# PCB_Telemetria_2020.net
KiCad netlist of a schematic drawn in EAGLE
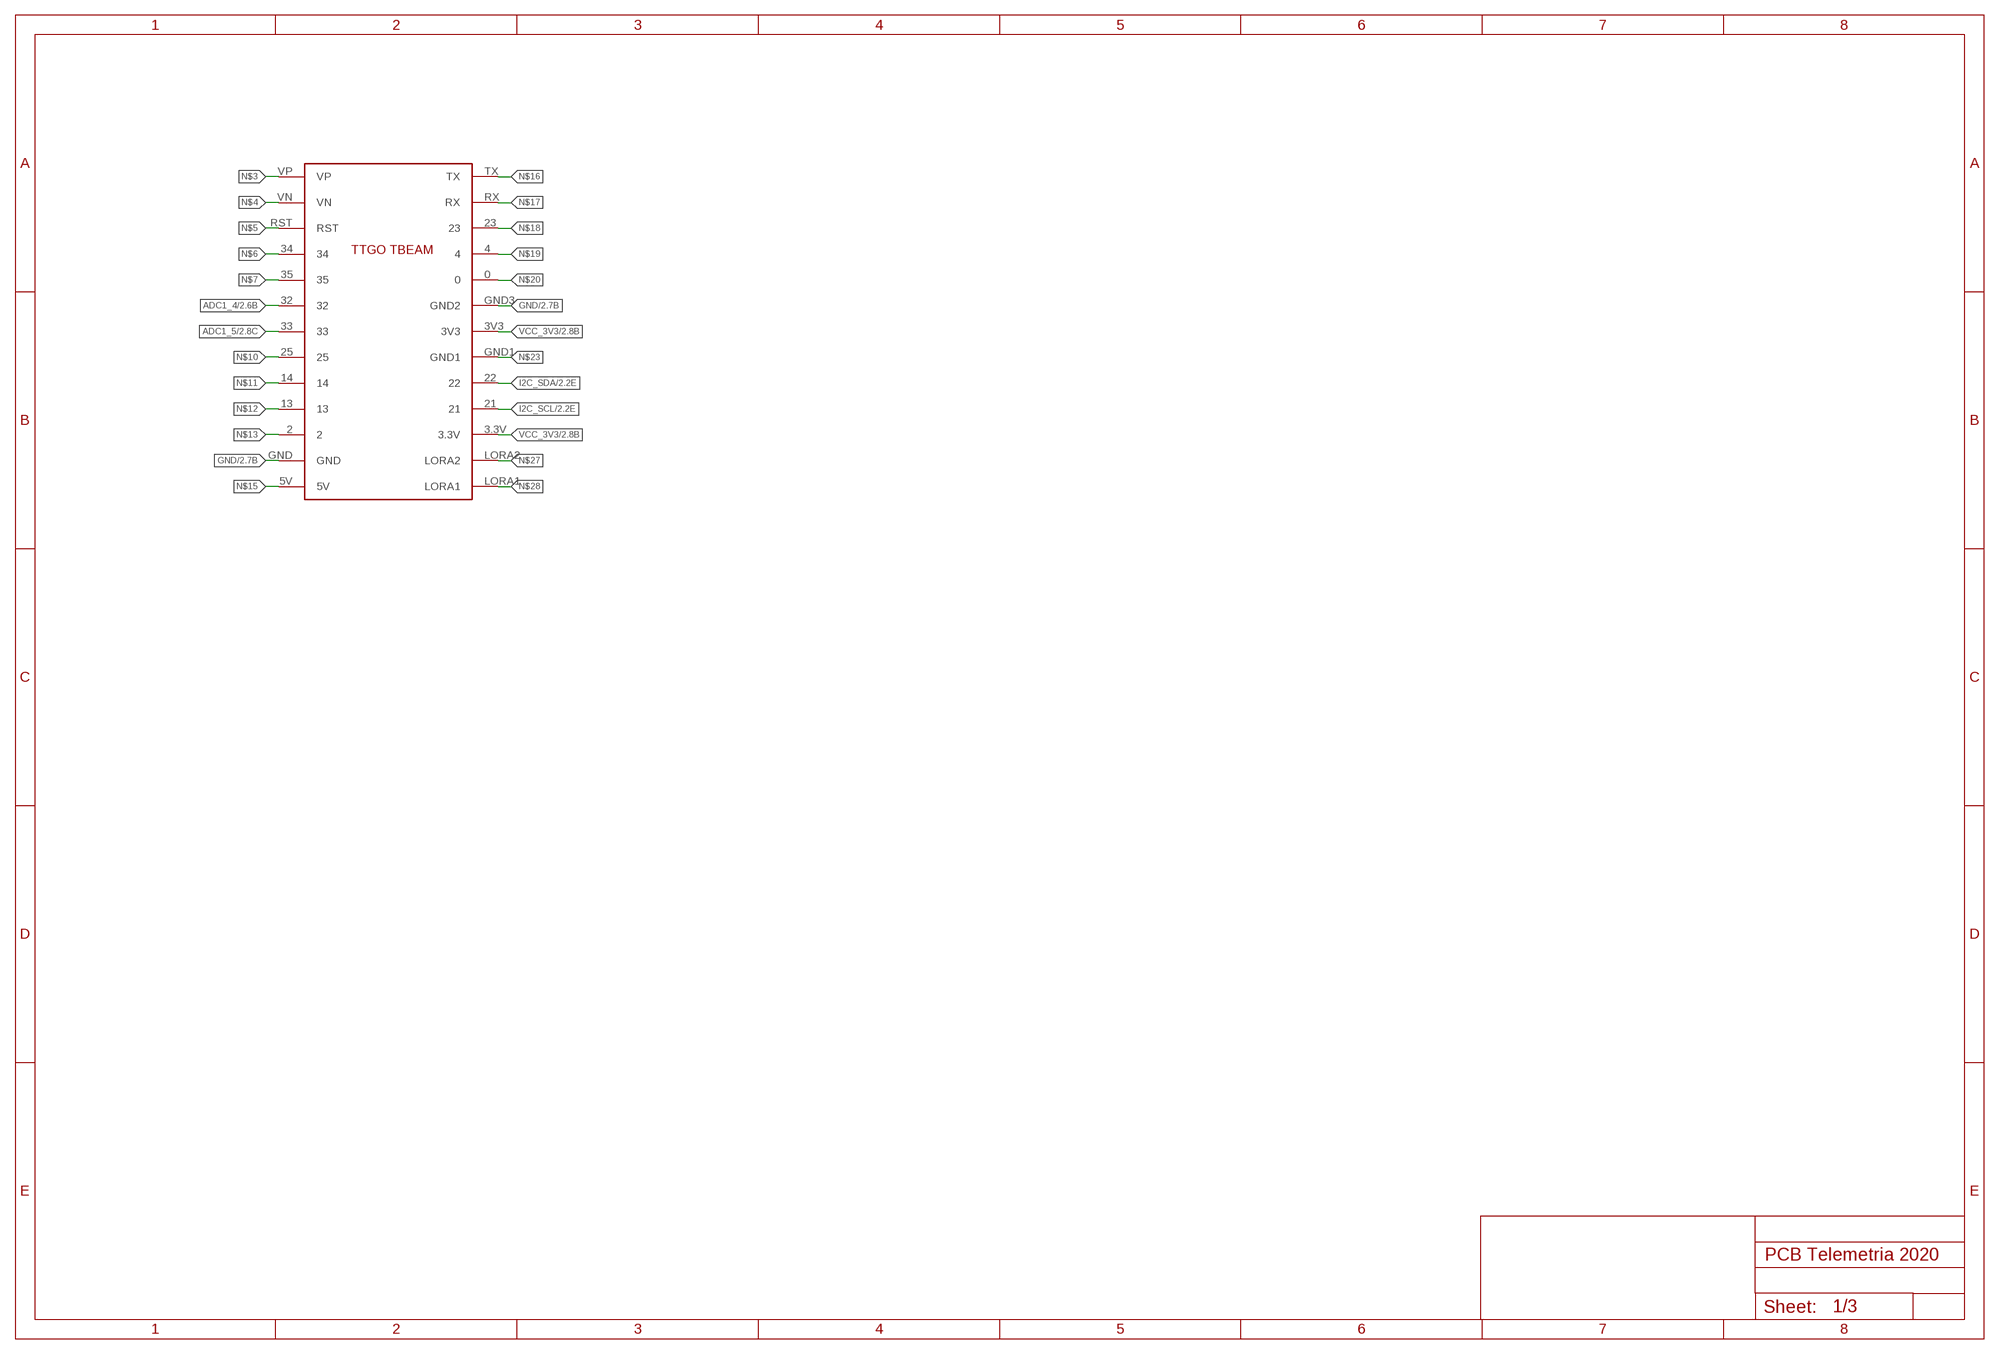
[diagram p0: schematic, sheet 1]
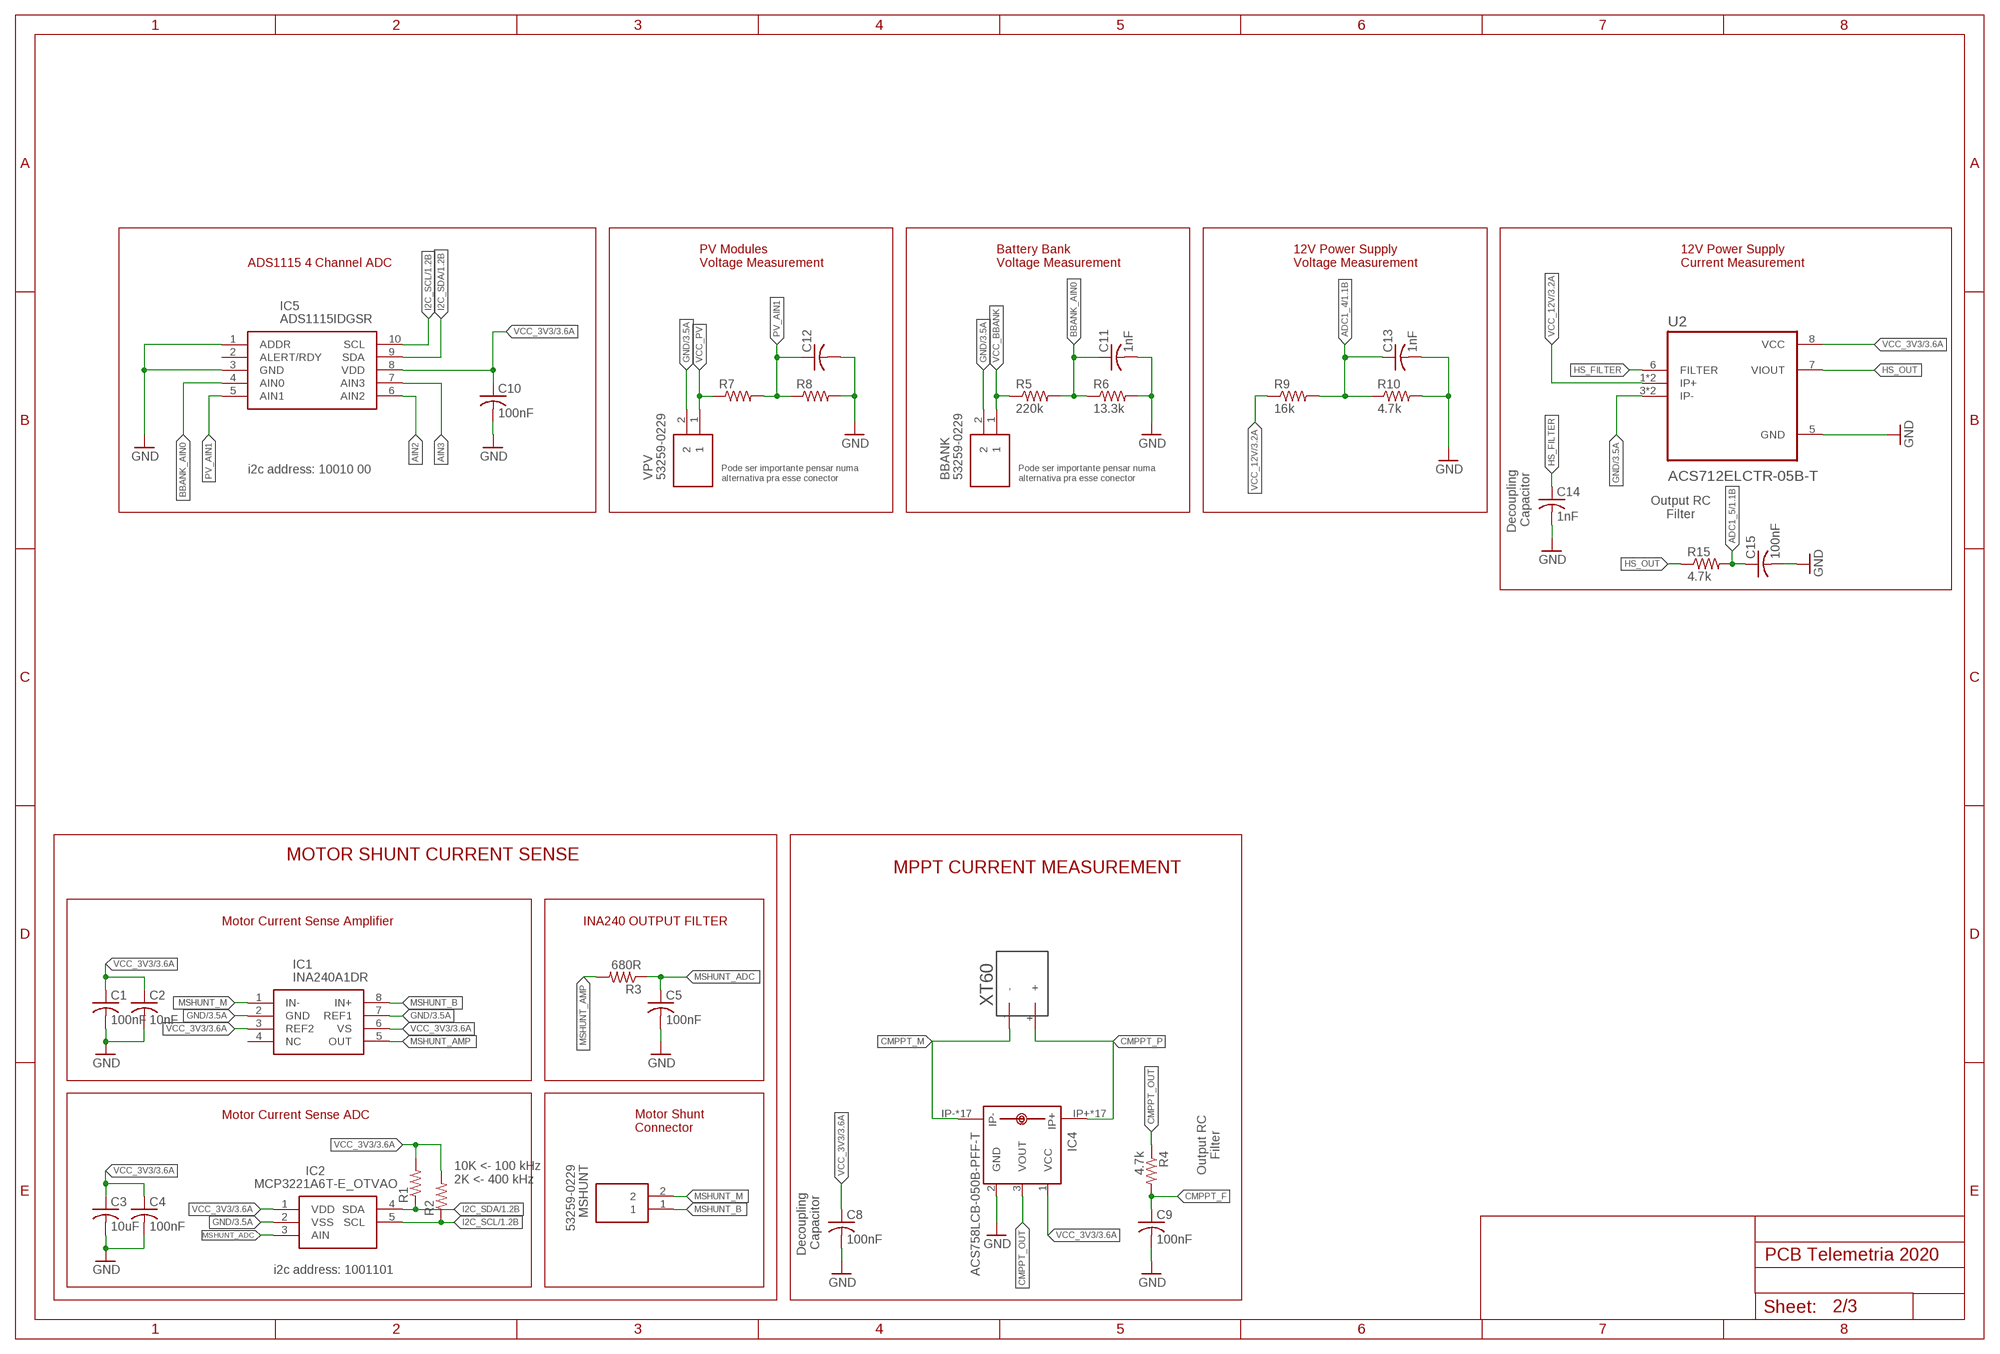
[diagram p1: schematic, sheet 2]
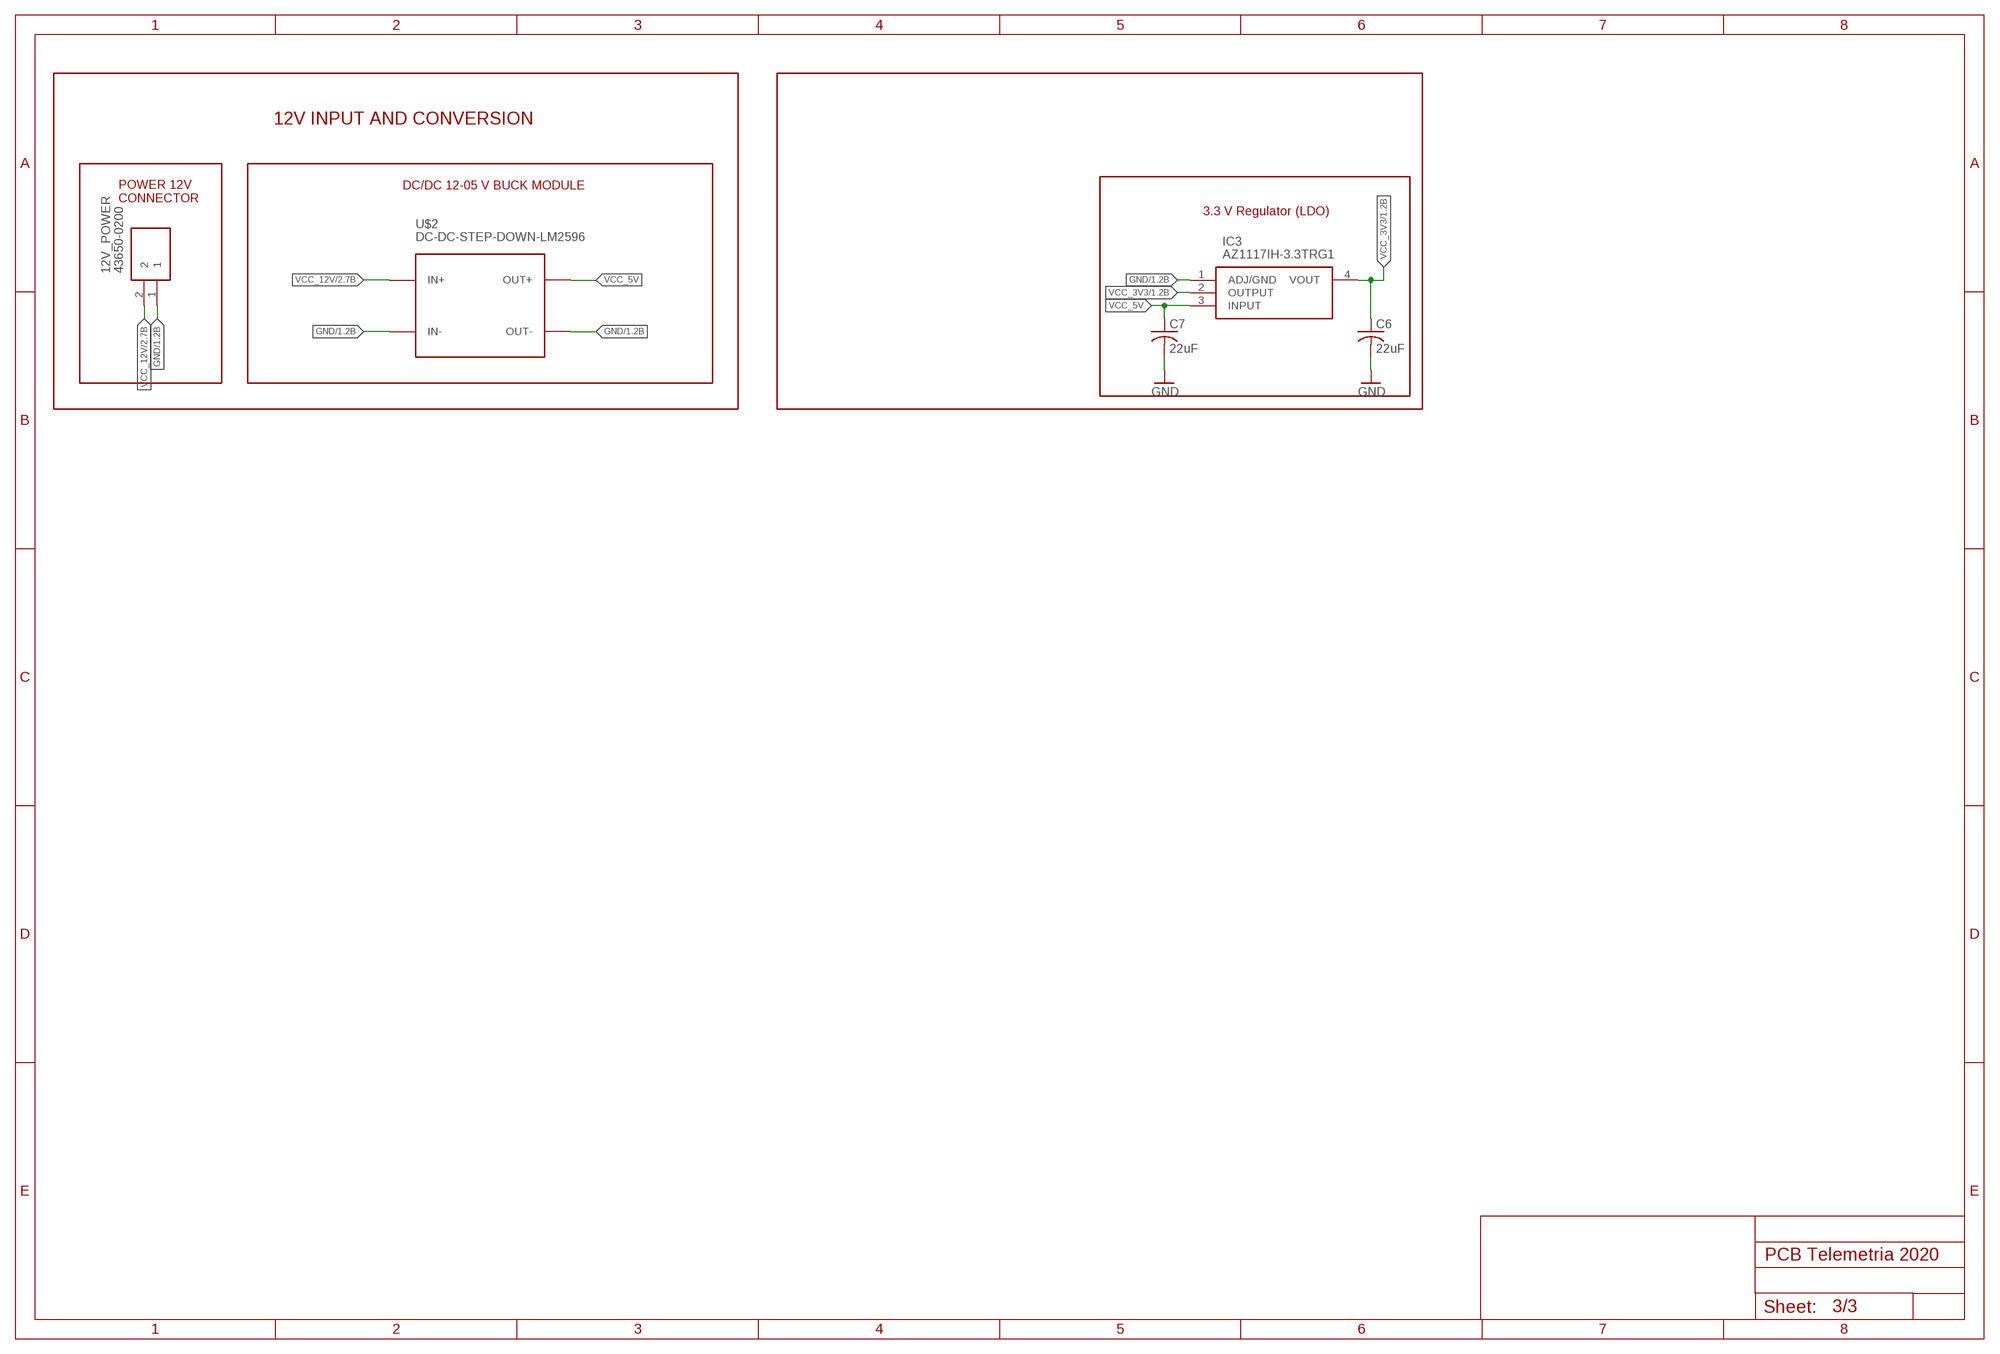
[diagram p2: schematic, sheet 3]

(export (version "E")
  (design (tool "Eeschema 10.0.6"))
  (components
    (comp (ref "BBANK")
      (value "53259-0229")
      (footprint "eagle-import:0532590229")
      (fields (field (name "MOUSER_PART_NUMBER") "538-53259-0229"))
      (libsource (lib "eagle-import") (part "53259-0229"))
    )
    (comp (ref "C1")
      (value "100nF")
      (footprint "eagle-import:C0805")
      (libsource (lib "eagle-import") (part "C-USC0805"))
    )
    (comp (ref "C2")
      (value "10nF")
      (footprint "eagle-import:C0805")
      (libsource (lib "eagle-import") (part "C-USC0805"))
    )
    (comp (ref "C3")
      (value "10uF")
      (footprint "eagle-import:C0805")
      (libsource (lib "eagle-import") (part "C-USC0805"))
    )
    (comp (ref "C4")
      (value "100nF")
      (footprint "eagle-import:C0805")
      (libsource (lib "eagle-import") (part "C-USC0805"))
    )
    (comp (ref "C5")
      (value "100nF")
      (footprint "eagle-import:C0805")
      (libsource (lib "eagle-import") (part "C-USC0805"))
    )
    (comp (ref "C8")
      (value "100nF")
      (footprint "eagle-import:C0805")
      (libsource (lib "eagle-import") (part "C-USC0805"))
    )
    (comp (ref "C9")
      (value "100nF")
      (footprint "eagle-import:C0805")
      (libsource (lib "eagle-import") (part "C-USC0805"))
    )
    (comp (ref "C10")
      (value "100nF")
      (footprint "eagle-import:C0805")
      (libsource (lib "eagle-import") (part "C-USC0805"))
    )
    (comp (ref "C11")
      (value "1nF")
      (footprint "eagle-import:C0805")
      (libsource (lib "eagle-import") (part "C-USC0805"))
    )
    (comp (ref "C12")
      (value "C-USC0805")
      (footprint "eagle-import:C0805")
      (libsource (lib "eagle-import") (part "C-USC0805"))
    )
    (comp (ref "C13")
      (value "1nF")
      (footprint "eagle-import:C0805")
      (libsource (lib "eagle-import") (part "C-USC0805"))
    )
    (comp (ref "C14")
      (value "1nF")
      (footprint "eagle-import:C0805")
      (libsource (lib "eagle-import") (part "C-USC0805"))
    )
    (comp (ref "C15")
      (value "100nF")
      (footprint "eagle-import:C0805")
      (libsource (lib "eagle-import") (part "C-USC0805"))
    )
    (comp (ref "IC1")
      (value "INA240A1DR")
      (footprint "eagle-import:SOIC127P600X175-8N")
      (fields (field (name "MOUSER_PART_NUMBER") "595-INA240A1DR"))
      (libsource (lib "eagle-import") (part "INA240A1DR"))
    )
    (comp (ref "IC2")
      (value "MCP3221A6T-E_OTVAO")
      (footprint "eagle-import:SOT95P280X145-5N")
      (fields
        (field (name "MANUFACTURER_PART_NUMBER") "MCP3221A6T-E/OTVAO")
        (field (name "MOUSER_PART_NUMBER") "579-MCP3221A6TEOTVAO")
      )
      (libsource (lib "eagle-import") (part "MCP3221A6T-E_OTVAO"))
    )
    (comp (ref "IC4")
      (value "ACS758LCB-050B-PFF-T")
      (footprint "eagle-import:CB-PFF")
      (libsource (lib "eagle-import") (part "ACS758LCB-050B-PFF-T"))
    )
    (comp (ref "IC5")
      (value "ADS1115IDGSR")
      (footprint "eagle-import:SOP50P490X110-10N")
      (fields (field (name "MOUSER_PART_NUMBER") "595-ADS1115IDGSR"))
      (libsource (lib "eagle-import") (part "ADS1115IDGSR"))
    )
    (comp (ref "MSHUNT")
      (value "53259-0229")
      (footprint "eagle-import:0532590229")
      (fields (field (name "MOUSER_PART_NUMBER") "538-53259-0229"))
      (libsource (lib "eagle-import") (part "53259-0229"))
    )
    (comp (ref "R1")
      (value "R-US_R0805")
      (footprint "eagle-import:R0805")
      (libsource (lib "eagle-import") (part "R-US_R0805"))
    )
    (comp (ref "R2")
      (value "R-US_R0805")
      (footprint "eagle-import:R0805")
      (libsource (lib "eagle-import") (part "R-US_R0805"))
    )
    (comp (ref "R3")
      (value "680R")
      (footprint "eagle-import:R0805")
      (libsource (lib "eagle-import") (part "R-US_R0805"))
    )
    (comp (ref "R4")
      (value "4.7k")
      (footprint "eagle-import:R0805")
      (libsource (lib "eagle-import") (part "R-US_R0805"))
    )
    (comp (ref "R5")
      (value "220k")
      (footprint "eagle-import:R0805")
      (libsource (lib "eagle-import") (part "R-US_R0805"))
    )
    (comp (ref "R6")
      (value "13.3k")
      (footprint "eagle-import:R0805")
      (libsource (lib "eagle-import") (part "R-US_R0805"))
    )
    (comp (ref "R7")
      (value "R-US_R0805")
      (footprint "eagle-import:R0805")
      (libsource (lib "eagle-import") (part "R-US_R0805"))
    )
    (comp (ref "R8")
      (value "R-US_R0805")
      (footprint "eagle-import:R0805")
      (libsource (lib "eagle-import") (part "R-US_R0805"))
    )
    (comp (ref "R9")
      (value "16k")
      (footprint "eagle-import:R0805")
      (libsource (lib "eagle-import") (part "R-US_R0805"))
    )
    (comp (ref "R10")
      (value "4.7k")
      (footprint "eagle-import:R0805")
      (libsource (lib "eagle-import") (part "R-US_R0805"))
    )
    (comp (ref "R15")
      (value "4.7k")
      (footprint "eagle-import:R0805")
      (libsource (lib "eagle-import") (part "R-US_R0805"))
    )
    (comp (ref "U$3")
      (value "XT60")
      (footprint "eagle-import:XT60")
      (libsource (lib "eagle-import") (part "XT60"))
    )
    (comp (ref "U2")
      (value "ACS712ELCTR-05B-T")
      (footprint "eagle-import:SOIC127P600X175-8N")
      (fields (field (name "MF") "Allegro MicroSystems LLC"))
      (libsource (lib "eagle-import") (part "ACS712ELCTR-05B-T"))
    )
    (comp (ref "VPV")
      (value "53259-0229")
      (footprint "eagle-import:0532590229")
      (fields (field (name "MOUSER_PART_NUMBER") "538-53259-0229"))
      (libsource (lib "eagle-import") (part "53259-0229"))
    )
    (comp (ref "U$1")
      (value "TTGOBEAM")
      (footprint "eagle-import:TTGOBEAM")
      (libsource (lib "eagle-import") (part "TTGOBEAM"))
    )
    (comp (ref "12V_POWER")
      (value "43650-0200")
      (footprint "eagle-import:43650-0200")
      (fields (field (name "MOUSER_PART_NUMBER") "538-43650-0200"))
      (libsource (lib "eagle-import") (part "43650-0200"))
    )
    (comp (ref "C6")
      (value "22uF")
      (footprint "eagle-import:C0805")
      (libsource (lib "eagle-import") (part "C-USC0805"))
    )
    (comp (ref "C7")
      (value "22uF")
      (footprint "eagle-import:C0805")
      (libsource (lib "eagle-import") (part "C-USC0805"))
    )
    (comp (ref "IC3")
      (value "AZ1117IH-3.3TRG1")
      (footprint "eagle-import:SOT230P700X170-4N")
      (fields (field (name "MOUSER_PART_NUMBER") "621-AZ1117IH-3.3TRG1"))
      (libsource (lib "eagle-import") (part "AZ1117IH-3.3TRG1"))
    )
    (comp (ref "U$2")
      (value "DC-DC-STEP-DOWN-LM2596")
      (footprint "eagle-import:DC-DC-STEP-DOWN-LM2596")
      (libsource (lib "eagle-import") (part "DC-DC-STEP-DOWN-LM2596"))
    )
  )
  (nets
    (net (code "1") (name "ADC1_4") (class "Default")
      (node (ref "C13") (pin "1") (pinfunction "1_1") (pintype "passive"))
      (node (ref "R10") (pin "1") (pinfunction "1_1") (pintype "passive"))
      (node (ref "R9") (pin "2") (pinfunction "2_2") (pintype "passive"))
      (node (ref "U$1") (pin "32") (pinfunction "32_32") (pintype "bidirectional"))
    )
    (net (code "2") (name "ADC1_5") (class "Default")
      (node (ref "C15") (pin "1") (pinfunction "1_1") (pintype "passive"))
      (node (ref "R15") (pin "2") (pinfunction "2_2") (pintype "passive"))
      (node (ref "U$1") (pin "33") (pinfunction "33_33") (pintype "bidirectional"))
    )
    (net (code "3") (name "AIN2") (class "Default")
      (node (ref "IC5") (pin "6") (pinfunction "AIN2_6") (pintype "bidirectional"))
    )
    (net (code "4") (name "AIN3") (class "Default")
      (node (ref "IC5") (pin "7") (pinfunction "AIN3_7") (pintype "bidirectional"))
    )
    (net (code "5") (name "BBANK_AIN0") (class "Default")
      (node (ref "C11") (pin "1") (pinfunction "1_1") (pintype "passive"))
      (node (ref "IC5") (pin "4") (pinfunction "AIN0_4") (pintype "bidirectional"))
      (node (ref "R5") (pin "2") (pinfunction "2_2") (pintype "passive"))
      (node (ref "R6") (pin "1") (pinfunction "1_1") (pintype "passive"))
    )
    (net (code "6") (name "CMPPT_F") (class "Default")
      (node (ref "C9") (pin "1") (pinfunction "1_1") (pintype "passive"))
      (node (ref "R4") (pin "2") (pinfunction "2_2") (pintype "passive"))
    )
    (net (code "7") (name "CMPPT_M") (class "Default")
      (node (ref "IC4") (pin "IP-") (pinfunction "IP-_IP-") (pintype "passive"))
      (node (ref "IC4") (pin "IP-@10") (pinfunction "IP-_IP-@10") (pintype "passive"))
      (node (ref "IC4") (pin "IP-@11") (pinfunction "IP-_IP-@11") (pintype "passive"))
      (node (ref "IC4") (pin "IP-@12") (pinfunction "IP-_IP-@12") (pintype "passive"))
      (node (ref "IC4") (pin "IP-@13") (pinfunction "IP-_IP-@13") (pintype "passive"))
      (node (ref "IC4") (pin "IP-@14") (pinfunction "IP-_IP-@14") (pintype "passive"))
      (node (ref "IC4") (pin "IP-@15") (pinfunction "IP-_IP-@15") (pintype "passive"))
      (node (ref "IC4") (pin "IP-@16") (pinfunction "IP-_IP-@16") (pintype "passive"))
      (node (ref "IC4") (pin "IP-@17") (pinfunction "IP-_IP-@17") (pintype "passive"))
      (node (ref "IC4") (pin "IP-@2") (pinfunction "IP-_IP-@2") (pintype "passive"))
      (node (ref "IC4") (pin "IP-@3") (pinfunction "IP-_IP-@3") (pintype "passive"))
      (node (ref "IC4") (pin "IP-@4") (pinfunction "IP-_IP-@4") (pintype "passive"))
      (node (ref "IC4") (pin "IP-@5") (pinfunction "IP-_IP-@5") (pintype "passive"))
      (node (ref "IC4") (pin "IP-@6") (pinfunction "IP-_IP-@6") (pintype "passive"))
      (node (ref "IC4") (pin "IP-@7") (pinfunction "IP-_IP-@7") (pintype "passive"))
      (node (ref "IC4") (pin "IP-@8") (pinfunction "IP-_IP-@8") (pintype "passive"))
      (node (ref "IC4") (pin "IP-@9") (pinfunction "IP-_IP-@9") (pintype "passive"))
      (node (ref "U$3") (pin "-") (pinfunction "-_-") (pintype "bidirectional"))
    )
    (net (code "8") (name "CMPPT_OUT") (class "Default")
      (node (ref "IC4") (pin "3") (pinfunction "VOUT_3") (pintype "output"))
      (node (ref "R4") (pin "1") (pinfunction "1_1") (pintype "passive"))
    )
    (net (code "9") (name "CMPPT_P") (class "Default")
      (node (ref "IC4") (pin "IP+") (pinfunction "IP+_IP+") (pintype "passive"))
      (node (ref "IC4") (pin "IP+@10") (pinfunction "IP+_IP+@10") (pintype "passive"))
      (node (ref "IC4") (pin "IP+@11") (pinfunction "IP+_IP+@11") (pintype "passive"))
      (node (ref "IC4") (pin "IP+@12") (pinfunction "IP+_IP+@12") (pintype "passive"))
      (node (ref "IC4") (pin "IP+@13") (pinfunction "IP+_IP+@13") (pintype "passive"))
      (node (ref "IC4") (pin "IP+@14") (pinfunction "IP+_IP+@14") (pintype "passive"))
      (node (ref "IC4") (pin "IP+@15") (pinfunction "IP+_IP+@15") (pintype "passive"))
      (node (ref "IC4") (pin "IP+@16") (pinfunction "IP+_IP+@16") (pintype "passive"))
      (node (ref "IC4") (pin "IP+@17") (pinfunction "IP+_IP+@17") (pintype "passive"))
      (node (ref "IC4") (pin "IP+@2") (pinfunction "IP+_IP+@2") (pintype "passive"))
      (node (ref "IC4") (pin "IP+@3") (pinfunction "IP+_IP+@3") (pintype "passive"))
      (node (ref "IC4") (pin "IP+@4") (pinfunction "IP+_IP+@4") (pintype "passive"))
      (node (ref "IC4") (pin "IP+@5") (pinfunction "IP+_IP+@5") (pintype "passive"))
      (node (ref "IC4") (pin "IP+@6") (pinfunction "IP+_IP+@6") (pintype "passive"))
      (node (ref "IC4") (pin "IP+@7") (pinfunction "IP+_IP+@7") (pintype "passive"))
      (node (ref "IC4") (pin "IP+@8") (pinfunction "IP+_IP+@8") (pintype "passive"))
      (node (ref "IC4") (pin "IP+@9") (pinfunction "IP+_IP+@9") (pintype "passive"))
      (node (ref "U$3") (pin "+") (pinfunction "+_+") (pintype "bidirectional"))
    )
    (net (code "10") (name "GND") (class "Default")
      (node (ref "12V_POWER") (pin "1") (pinfunction "1_1") (pintype "bidirectional"))
      (node (ref "BBANK") (pin "2") (pinfunction "2_2") (pintype "bidirectional"))
      (node (ref "C1") (pin "2") (pinfunction "2_2") (pintype "passive"))
      (node (ref "C10") (pin "2") (pinfunction "2_2") (pintype "passive"))
      (node (ref "C11") (pin "2") (pinfunction "2_2") (pintype "passive"))
      (node (ref "C12") (pin "2") (pinfunction "2_2") (pintype "passive"))
      (node (ref "C13") (pin "2") (pinfunction "2_2") (pintype "passive"))
      (node (ref "C14") (pin "2") (pinfunction "2_2") (pintype "passive"))
      (node (ref "C15") (pin "2") (pinfunction "2_2") (pintype "passive"))
      (node (ref "C2") (pin "2") (pinfunction "2_2") (pintype "passive"))
      (node (ref "C3") (pin "2") (pinfunction "2_2") (pintype "passive"))
      (node (ref "C4") (pin "2") (pinfunction "2_2") (pintype "passive"))
      (node (ref "C5") (pin "2") (pinfunction "2_2") (pintype "passive"))
      (node (ref "C6") (pin "2") (pinfunction "2_2") (pintype "passive"))
      (node (ref "C7") (pin "2") (pinfunction "2_2") (pintype "passive"))
      (node (ref "C8") (pin "2") (pinfunction "2_2") (pintype "passive"))
      (node (ref "C9") (pin "2") (pinfunction "2_2") (pintype "passive"))
      (node (ref "IC1") (pin "2") (pinfunction "GND_2") (pintype "bidirectional"))
      (node (ref "IC1") (pin "7") (pinfunction "REF1_7") (pintype "bidirectional"))
      (node (ref "IC2") (pin "2") (pinfunction "VSS_2") (pintype "bidirectional"))
      (node (ref "IC3") (pin "1") (pinfunction "ADJ/GND_1") (pintype "bidirectional"))
      (node (ref "IC4") (pin "2") (pinfunction "GND_2") (pintype "power_in"))
      (node (ref "IC5") (pin "1") (pinfunction "ADDR_1") (pintype "bidirectional"))
      (node (ref "IC5") (pin "3") (pinfunction "GND_3") (pintype "bidirectional"))
      (node (ref "R10") (pin "2") (pinfunction "2_2") (pintype "passive"))
      (node (ref "R6") (pin "2") (pinfunction "2_2") (pintype "passive"))
      (node (ref "R8") (pin "2") (pinfunction "2_2") (pintype "passive"))
      (node (ref "U$1") (pin "GND") (pinfunction "GND_GND") (pintype "bidirectional"))
      (node (ref "U$1") (pin "GND3") (pinfunction "GND2_GND3") (pintype "bidirectional"))
      (node (ref "U$2") (pin "IN-") (pinfunction "IN-_IN-") (pintype "bidirectional"))
      (node (ref "U$2") (pin "OUT-") (pinfunction "OUT-_OUT-") (pintype "bidirectional"))
      (node (ref "U2") (pin "3") (pinfunction "IP-_3") (pintype "input"))
      (node (ref "U2") (pin "4") (pinfunction "IP-_4") (pintype "input"))
      (node (ref "U2") (pin "5") (pinfunction "GND_5") (pintype "power_in"))
      (node (ref "VPV") (pin "2") (pinfunction "2_2") (pintype "bidirectional"))
    )
    (net (code "11") (name "HS_FILTER") (class "Default")
      (node (ref "C14") (pin "1") (pinfunction "1_1") (pintype "passive"))
      (node (ref "U2") (pin "6") (pinfunction "FILTER_6") (pintype "input"))
    )
    (net (code "12") (name "HS_OUT") (class "Default")
      (node (ref "R15") (pin "1") (pinfunction "1_1") (pintype "passive"))
      (node (ref "U2") (pin "7") (pinfunction "VIOUT_7") (pintype "output"))
    )
    (net (code "13") (name "I2C_SCL") (class "Default")
      (node (ref "IC2") (pin "5") (pinfunction "SCL_5") (pintype "bidirectional"))
      (node (ref "IC5") (pin "10") (pinfunction "SCL_10") (pintype "bidirectional"))
      (node (ref "R2") (pin "1") (pinfunction "1_1") (pintype "passive"))
      (node (ref "U$1") (pin "21") (pinfunction "21_21") (pintype "bidirectional"))
    )
    (net (code "14") (name "I2C_SDA") (class "Default")
      (node (ref "IC2") (pin "4") (pinfunction "SDA_4") (pintype "bidirectional"))
      (node (ref "IC5") (pin "9") (pinfunction "SDA_9") (pintype "bidirectional"))
      (node (ref "R1") (pin "1") (pinfunction "1_1") (pintype "passive"))
      (node (ref "U$1") (pin "22") (pinfunction "22_22") (pintype "bidirectional"))
    )
    (net (code "15") (name "MSHUNT_ADC") (class "Default")
      (node (ref "C5") (pin "1") (pinfunction "1_1") (pintype "passive"))
      (node (ref "IC2") (pin "3") (pinfunction "AIN_3") (pintype "bidirectional"))
      (node (ref "R3") (pin "1") (pinfunction "1_1") (pintype "passive"))
    )
    (net (code "16") (name "MSHUNT_AMP") (class "Default")
      (node (ref "IC1") (pin "5") (pinfunction "OUT_5") (pintype "bidirectional"))
      (node (ref "R3") (pin "2") (pinfunction "2_2") (pintype "passive"))
    )
    (net (code "17") (name "MSHUNT_B") (class "Default")
      (node (ref "IC1") (pin "8") (pinfunction "IN+_8") (pintype "bidirectional"))
      (node (ref "MSHUNT") (pin "1") (pinfunction "1_1") (pintype "bidirectional"))
    )
    (net (code "18") (name "MSHUNT_M") (class "Default")
      (node (ref "IC1") (pin "1") (pinfunction "IN-_1") (pintype "bidirectional"))
      (node (ref "MSHUNT") (pin "2") (pinfunction "2_2") (pintype "bidirectional"))
    )
    (net (code "19") (name "N$3") (class "Default")
      (node (ref "U$1") (pin "VP") (pinfunction "VP_VP") (pintype "bidirectional"))
    )
    (net (code "20") (name "N$4") (class "Default")
      (node (ref "U$1") (pin "VN") (pinfunction "VN_VN") (pintype "bidirectional"))
    )
    (net (code "21") (name "N$5") (class "Default")
      (node (ref "U$1") (pin "RST") (pinfunction "RST_RST") (pintype "bidirectional"))
    )
    (net (code "22") (name "N$6") (class "Default")
      (node (ref "U$1") (pin "34") (pinfunction "34_34") (pintype "bidirectional"))
    )
    (net (code "23") (name "N$7") (class "Default")
      (node (ref "U$1") (pin "35") (pinfunction "35_35") (pintype "bidirectional"))
    )
    (net (code "24") (name "N$10") (class "Default")
      (node (ref "U$1") (pin "25") (pinfunction "25_25") (pintype "bidirectional"))
    )
    (net (code "25") (name "N$11") (class "Default")
      (node (ref "U$1") (pin "14") (pinfunction "14_14") (pintype "bidirectional"))
    )
    (net (code "26") (name "N$12") (class "Default")
      (node (ref "U$1") (pin "13") (pinfunction "13_13") (pintype "bidirectional"))
    )
    (net (code "27") (name "N$13") (class "Default")
      (node (ref "U$1") (pin "2") (pinfunction "2_2") (pintype "bidirectional"))
    )
    (net (code "28") (name "N$15") (class "Default")
      (node (ref "U$1") (pin "5V") (pinfunction "5V_5V") (pintype "bidirectional"))
    )
    (net (code "29") (name "N$16") (class "Default")
      (node (ref "U$1") (pin "TX") (pinfunction "TX_TX") (pintype "bidirectional"))
    )
    (net (code "30") (name "N$17") (class "Default")
      (node (ref "U$1") (pin "RX") (pinfunction "RX_RX") (pintype "bidirectional"))
    )
    (net (code "31") (name "N$18") (class "Default")
      (node (ref "U$1") (pin "23") (pinfunction "23_23") (pintype "bidirectional"))
    )
    (net (code "32") (name "N$19") (class "Default")
      (node (ref "U$1") (pin "4") (pinfunction "4_4") (pintype "bidirectional"))
    )
    (net (code "33") (name "N$20") (class "Default")
      (node (ref "U$1") (pin "0") (pinfunction "0_0") (pintype "bidirectional"))
    )
    (net (code "34") (name "N$23") (class "Default")
      (node (ref "U$1") (pin "GND1") (pinfunction "GND1_GND1") (pintype "bidirectional"))
    )
    (net (code "35") (name "N$27") (class "Default")
      (node (ref "U$1") (pin "LORA2") (pinfunction "LORA2_LORA2") (pintype "bidirectional"))
    )
    (net (code "36") (name "N$28") (class "Default")
      (node (ref "U$1") (pin "LORA1") (pinfunction "LORA1_LORA1") (pintype "bidirectional"))
    )
    (net (code "37") (name "PV_AIN1") (class "Default")
      (node (ref "C12") (pin "1") (pinfunction "1_1") (pintype "passive"))
      (node (ref "IC5") (pin "5") (pinfunction "AIN1_5") (pintype "bidirectional"))
      (node (ref "R7") (pin "2") (pinfunction "2_2") (pintype "passive"))
      (node (ref "R8") (pin "1") (pinfunction "1_1") (pintype "passive"))
    )
    (net (code "38") (name "VCC_3V3") (class "Default")
      (node (ref "C1") (pin "1") (pinfunction "1_1") (pintype "passive"))
      (node (ref "C10") (pin "1") (pinfunction "1_1") (pintype "passive"))
      (node (ref "C2") (pin "1") (pinfunction "1_1") (pintype "passive"))
      (node (ref "C3") (pin "1") (pinfunction "1_1") (pintype "passive"))
      (node (ref "C4") (pin "1") (pinfunction "1_1") (pintype "passive"))
      (node (ref "C6") (pin "1") (pinfunction "1_1") (pintype "passive"))
      (node (ref "C8") (pin "1") (pinfunction "1_1") (pintype "passive"))
      (node (ref "IC1") (pin "3") (pinfunction "REF2_3") (pintype "bidirectional"))
      (node (ref "IC1") (pin "6") (pinfunction "VS_6") (pintype "bidirectional"))
      (node (ref "IC2") (pin "1") (pinfunction "VDD_1") (pintype "bidirectional"))
      (node (ref "IC3") (pin "2") (pinfunction "OUTPUT_2") (pintype "bidirectional"))
      (node (ref "IC3") (pin "4") (pinfunction "VOUT_4") (pintype "bidirectional"))
      (node (ref "IC4") (pin "1") (pinfunction "VCC_1") (pintype "power_in"))
      (node (ref "IC5") (pin "8") (pinfunction "VDD_8") (pintype "bidirectional"))
      (node (ref "R1") (pin "2") (pinfunction "2_2") (pintype "passive"))
      (node (ref "R2") (pin "2") (pinfunction "2_2") (pintype "passive"))
      (node (ref "U$1") (pin "3.3V") (pinfunction "3.3V_3.3V") (pintype "bidirectional"))
      (node (ref "U$1") (pin "3V3") (pinfunction "3V3_3V3") (pintype "bidirectional"))
      (node (ref "U2") (pin "8") (pinfunction "VCC_8") (pintype "power_in"))
    )
    (net (code "39") (name "VCC_5V") (class "Default")
      (node (ref "C7") (pin "1") (pinfunction "1_1") (pintype "passive"))
      (node (ref "IC3") (pin "3") (pinfunction "INPUT_3") (pintype "bidirectional"))
      (node (ref "U$2") (pin "OUT+") (pinfunction "OUT+_OUT+") (pintype "bidirectional"))
    )
    (net (code "40") (name "VCC_12V") (class "Default")
      (node (ref "12V_POWER") (pin "2") (pinfunction "2_2") (pintype "bidirectional"))
      (node (ref "R9") (pin "1") (pinfunction "1_1") (pintype "passive"))
      (node (ref "U$2") (pin "IN+") (pinfunction "IN+_IN+") (pintype "bidirectional"))
      (node (ref "U2") (pin "1") (pinfunction "IP+_1") (pintype "input"))
      (node (ref "U2") (pin "2") (pinfunction "IP+_2") (pintype "input"))
    )
    (net (code "41") (name "VCC_BBANK") (class "Default")
      (node (ref "BBANK") (pin "1") (pinfunction "1_1") (pintype "bidirectional"))
      (node (ref "R5") (pin "1") (pinfunction "1_1") (pintype "passive"))
    )
    (net (code "42") (name "VCC_PV") (class "Default")
      (node (ref "R7") (pin "1") (pinfunction "1_1") (pintype "passive"))
      (node (ref "VPV") (pin "1") (pinfunction "1_1") (pintype "bidirectional"))
    )
    (net (code "43") (name "unconnected-(IC1-NC-Pad4)") (class "Default")
      (node (ref "IC1") (pin "4") (pinfunction "NC_4") (pintype "no_connect"))
    )
    (net (code "44") (name "unconnected-(IC5-ALERT{slash}RDY-Pad2)") (class "Default")
      (node (ref "IC5") (pin "2") (pinfunction "ALERT/RDY_2") (pintype "bidirectional"))
    )
  )
)
